# DDR_HDMI.net
KiCad netlist of a schematic drawn in Altium Designer
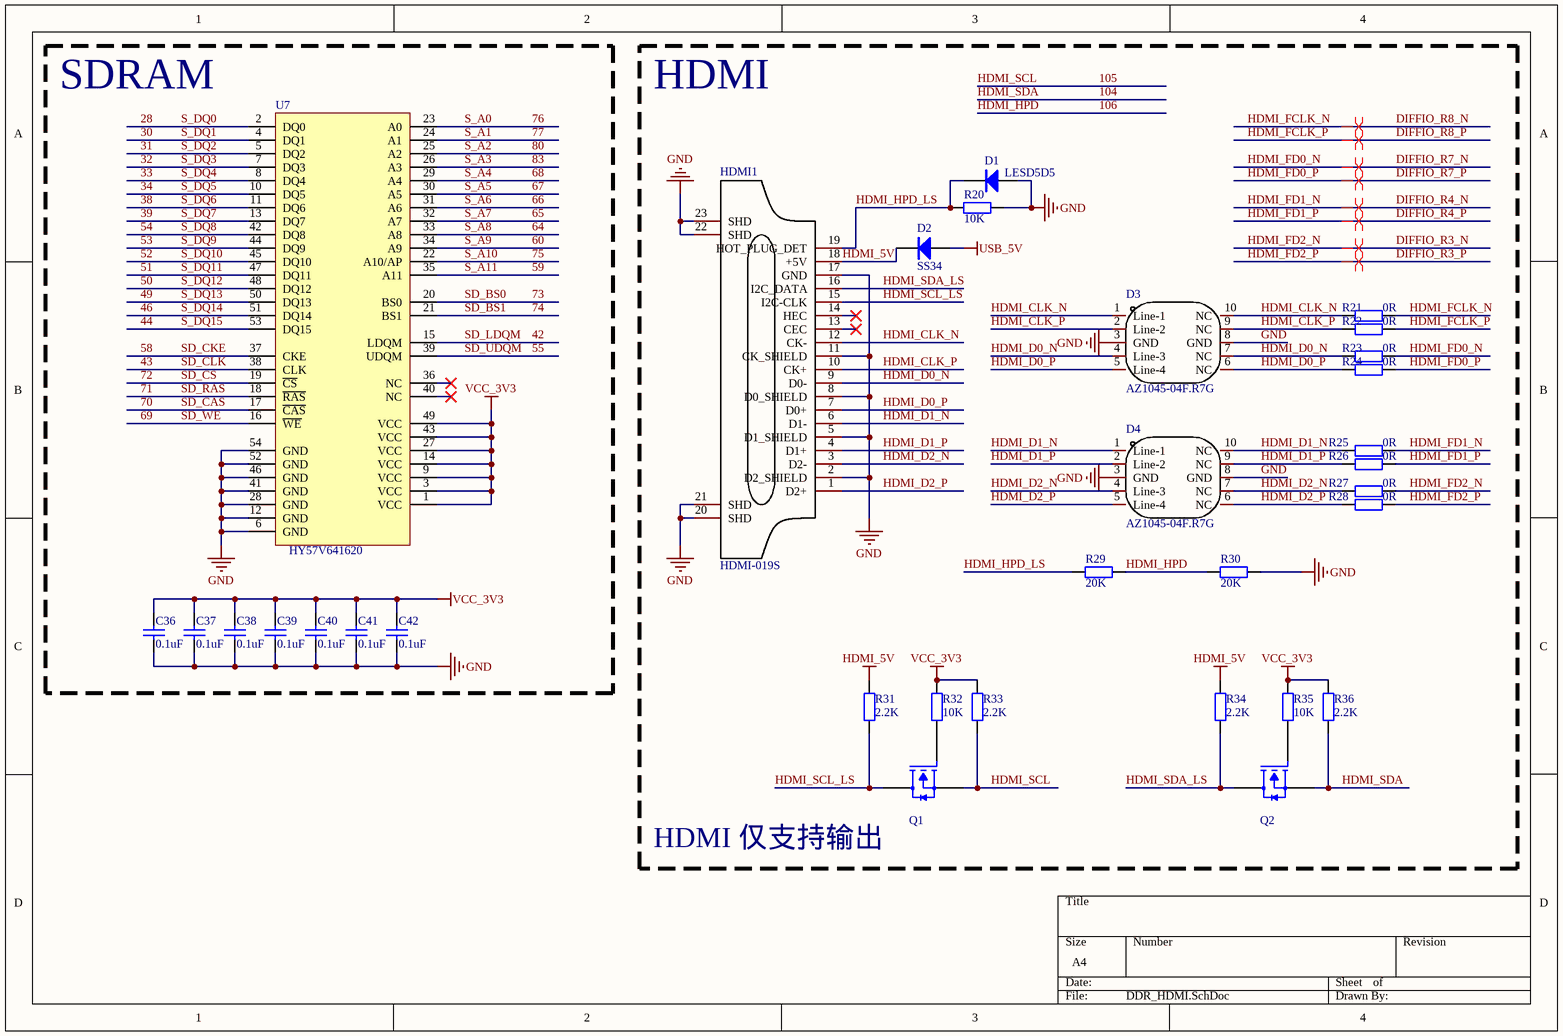
[diagram p0: DDR_HDMI.SchDoc]

(export (version "E")
  (design (tool "Eeschema 10.0.6"))
  (components
    (comp (ref "C36")
      (value "0.1uF")
      (footprint "0402_C")
      (description "贴片电容")
      (libsource (lib "My_Devices") (part "0402_C"))
    )
    (comp (ref "C37")
      (value "0.1uF")
      (footprint "0402_C")
      (description "贴片电容")
      (libsource (lib "My_Devices") (part "0402_C"))
    )
    (comp (ref "C38")
      (value "0.1uF")
      (footprint "0402_C")
      (description "贴片电容")
      (libsource (lib "My_Devices") (part "0402_C"))
    )
    (comp (ref "C39")
      (value "0.1uF")
      (footprint "0402_C")
      (description "贴片电容")
      (libsource (lib "My_Devices") (part "0402_C"))
    )
    (comp (ref "C40")
      (value "0.1uF")
      (footprint "0402_C")
      (description "贴片电容")
      (libsource (lib "My_Devices") (part "0402_C"))
    )
    (comp (ref "C41")
      (value "0.1uF")
      (footprint "0402_C")
      (description "贴片电容")
      (libsource (lib "My_Devices") (part "0402_C"))
    )
    (comp (ref "C42")
      (value "0.1uF")
      (footprint "0402_C")
      (description "贴片电容")
      (libsource (lib "My_Devices") (part "0402_C"))
    )
    (comp (ref "D1")
      (value "LESD5D5")
      (footprint "SOD-523_L1.2-W0.8-LS1.6-RD")
      (description "肖特基二极管")
      (fields (field (name "版权归属") "源创客"))
      (libsource (lib "My_Devices") (part "1N5819"))
    )
    (comp (ref "D2")
      (value "SS34")
      (footprint "SMC")
      (description "肖特基二极管")
      (fields (field (name "版权归属") "源创客"))
      (libsource (lib "My_Devices") (part "SS34"))
    )
    (comp (ref "D3")
      (value "AZ1045-04F.R7G")
      (footprint "DFN2510-10_L2.5-W1.0-P0.50-BL")
      (description "反向截止电压(Vrwm):5V;击穿电压:6V;最大钳位电压:12V;")
      (fields (field (name "MANUFACTURER") "AMAZING(晶焱)") (field (name "NAME") "AZ1045-04F.R7G"))
      (libsource (lib "Schlib1") (part "AZ1045-04F.R7G"))
    )
    (comp (ref "D4")
      (value "AZ1045-04F.R7G")
      (footprint "DFN2510-10_L2.5-W1.0-P0.50-BL")
      (description "反向截止电压(Vrwm):5V;击穿电压:6V;最大钳位电压:12V;")
      (fields (field (name "MANUFACTURER") "AMAZING(晶焱)") (field (name "NAME") "AZ1045-04F.R7G"))
      (libsource (lib "Schlib1") (part "AZ1045-04F.R7G"))
    )
    (comp (ref "HDMI1")
      (value "HDMI-019S")
      (footprint "HDMI-SMD_HDMI-019S")
      (description "连接器类型:HDMI;公母:母;总PIN位数:19;排数:-;安装方式:卧贴;额定电流:500mA;工作温度范围:-25℃~+75℃;")
      (fields (field (name "MANUFACTURER") "SOFNG(硕方)") (field (name "NAME") "HDMI-019S"))
      (libsource (lib "Schlib1") (part "HDMI-019S"))
    )
    (comp (ref "Q1")
      (value "AO3400A")
      (footprint "SOT23-3")
      (description "N-MOS")
      (libsource (lib "Schlib1") (part "AO3400A"))
    )
    (comp (ref "Q2")
      (value "AO3400A")
      (footprint "SOT23-3")
      (description "N-MOS")
      (libsource (lib "Schlib1") (part "AO3400A"))
    )
    (comp (ref "R20")
      (value "10K")
      (footprint "0402_R")
      (description "贴片电阻")
      (libsource (lib "") (part "0402_R_1"))
    )
    (comp (ref "R21")
      (value "0R")
      (footprint "0402_R")
      (description "贴片电阻")
      (libsource (lib "") (part "0402_R_1"))
    )
    (comp (ref "R22")
      (value "0R")
      (footprint "0402_R")
      (description "贴片电阻")
      (libsource (lib "") (part "0402_R_1"))
    )
    (comp (ref "R23")
      (value "0R")
      (footprint "0402_R")
      (description "贴片电阻")
      (libsource (lib "") (part "0402_R_1"))
    )
    (comp (ref "R24")
      (value "0R")
      (footprint "0402_R")
      (description "贴片电阻")
      (libsource (lib "") (part "0402_R_1"))
    )
    (comp (ref "R25")
      (value "0R")
      (footprint "0402_R")
      (description "贴片电阻")
      (libsource (lib "") (part "0402_R_1"))
    )
    (comp (ref "R26")
      (value "0R")
      (footprint "0402_R")
      (description "贴片电阻")
      (libsource (lib "") (part "0402_R_1"))
    )
    (comp (ref "R27")
      (value "0R")
      (footprint "0402_R")
      (description "贴片电阻")
      (libsource (lib "") (part "0402_R_1"))
    )
    (comp (ref "R28")
      (value "0R")
      (footprint "0402_R")
      (description "贴片电阻")
      (libsource (lib "") (part "0402_R_1"))
    )
    (comp (ref "R29")
      (value "20K")
      (footprint "0402_R")
      (description "贴片电阻")
      (libsource (lib "") (part "0402_R_1"))
    )
    (comp (ref "R30")
      (value "20K")
      (footprint "0402_R")
      (description "贴片电阻")
      (libsource (lib "") (part "0402_R_1"))
    )
    (comp (ref "R31")
      (value "2.2K")
      (footprint "0402_R")
      (description "贴片电阻")
      (libsource (lib "My_Devices") (part "0402_R"))
    )
    (comp (ref "R32")
      (value "10K")
      (footprint "0402_R")
      (description "贴片电阻")
      (libsource (lib "My_Devices") (part "0402_R"))
    )
    (comp (ref "R33")
      (value "2.2K")
      (footprint "0402_R")
      (description "贴片电阻")
      (libsource (lib "My_Devices") (part "0402_R"))
    )
    (comp (ref "R34")
      (value "2.2K")
      (footprint "0402_R")
      (description "贴片电阻")
      (libsource (lib "My_Devices") (part "0402_R"))
    )
    (comp (ref "R35")
      (value "10K")
      (footprint "0402_R")
      (description "贴片电阻")
      (libsource (lib "My_Devices") (part "0402_R"))
    )
    (comp (ref "R36")
      (value "2.2K")
      (footprint "0402_R")
      (description "贴片电阻")
      (libsource (lib "My_Devices") (part "0402_R"))
    )
    (comp (ref "U7")
      (value "HY57V641620")
      (footprint "TSOP-54_L22.2-W10.2-P0.80-LS11.8-BL")
      (libsource (lib "Schlib1") (part "HY57V641620"))
    )
  )
  (nets
    (net (code "1") (name "/28") (class "Default")
      (node (ref "U7") (pin "2") (pinfunction "DQ0_2") (pintype "passive"))
    )
    (net (code "2") (name "/30") (class "Default")
      (node (ref "U7") (pin "4") (pinfunction "DQ1_4") (pintype "passive"))
    )
    (net (code "3") (name "/31") (class "Default")
      (node (ref "U7") (pin "5") (pinfunction "DQ2_5") (pintype "passive"))
    )
    (net (code "4") (name "/32") (class "Default")
      (node (ref "U7") (pin "7") (pinfunction "DQ3_7") (pintype "passive"))
    )
    (net (code "5") (name "/33") (class "Default")
      (node (ref "U7") (pin "8") (pinfunction "DQ4_8") (pintype "passive"))
    )
    (net (code "6") (name "/34") (class "Default")
      (node (ref "U7") (pin "10") (pinfunction "DQ5_10") (pintype "passive"))
    )
    (net (code "7") (name "/38") (class "Default")
      (node (ref "U7") (pin "11") (pinfunction "DQ6_11") (pintype "passive"))
    )
    (net (code "8") (name "/39") (class "Default")
      (node (ref "U7") (pin "13") (pinfunction "DQ7_13") (pintype "passive"))
    )
    (net (code "9") (name "/42") (class "Default")
      (node (ref "U7") (pin "15") (pinfunction "LDQM_15") (pintype "power_in"))
    )
    (net (code "10") (name "/43") (class "Default")
      (node (ref "U7") (pin "38") (pinfunction "CLK_38") (pintype "passive"))
    )
    (net (code "11") (name "/44") (class "Default")
      (node (ref "U7") (pin "53") (pinfunction "DQ15_53") (pintype "passive"))
    )
    (net (code "12") (name "/46") (class "Default")
      (node (ref "U7") (pin "51") (pinfunction "DQ14_51") (pintype "passive"))
    )
    (net (code "13") (name "/49") (class "Default")
      (node (ref "U7") (pin "50") (pinfunction "DQ13_50") (pintype "passive"))
    )
    (net (code "14") (name "/50") (class "Default")
      (node (ref "U7") (pin "48") (pinfunction "DQ12_48") (pintype "passive"))
    )
    (net (code "15") (name "/51") (class "Default")
      (node (ref "U7") (pin "47") (pinfunction "DQ11_47") (pintype "passive"))
    )
    (net (code "16") (name "/52") (class "Default")
      (node (ref "U7") (pin "45") (pinfunction "DQ10_45") (pintype "passive"))
    )
    (net (code "17") (name "/53") (class "Default")
      (node (ref "U7") (pin "44") (pinfunction "DQ9_44") (pintype "passive"))
    )
    (net (code "18") (name "/54") (class "Default")
      (node (ref "U7") (pin "42") (pinfunction "DQ8_42") (pintype "passive"))
    )
    (net (code "19") (name "/55") (class "Default")
      (node (ref "U7") (pin "39") (pinfunction "UDQM_39") (pintype "power_in"))
    )
    (net (code "20") (name "/58") (class "Default")
      (node (ref "U7") (pin "37") (pinfunction "CKE_37") (pintype "passive"))
    )
    (net (code "21") (name "/59") (class "Default")
      (node (ref "U7") (pin "35") (pinfunction "A11_35") (pintype "power_in"))
    )
    (net (code "22") (name "/60") (class "Default")
      (node (ref "U7") (pin "34") (pinfunction "A9_34") (pintype "power_in"))
    )
    (net (code "23") (name "/64") (class "Default")
      (node (ref "U7") (pin "33") (pinfunction "A8_33") (pintype "power_in"))
    )
    (net (code "24") (name "/65") (class "Default")
      (node (ref "U7") (pin "32") (pinfunction "A7_32") (pintype "power_in"))
    )
    (net (code "25") (name "/66") (class "Default")
      (node (ref "U7") (pin "31") (pinfunction "A6_31") (pintype "power_in"))
    )
    (net (code "26") (name "/67") (class "Default")
      (node (ref "U7") (pin "30") (pinfunction "A5_30") (pintype "power_in"))
    )
    (net (code "27") (name "/68") (class "Default")
      (node (ref "U7") (pin "29") (pinfunction "A4_29") (pintype "power_in"))
    )
    (net (code "28") (name "/69") (class "Default")
      (node (ref "U7") (pin "16") (pinfunction "~{WE}_16") (pintype "power_in"))
    )
    (net (code "29") (name "/70") (class "Default")
      (node (ref "U7") (pin "17") (pinfunction "~{CAS}_17") (pintype "power_in"))
    )
    (net (code "30") (name "/71") (class "Default")
      (node (ref "U7") (pin "18") (pinfunction "~{RAS}_18") (pintype "power_in"))
    )
    (net (code "31") (name "/72") (class "Default")
      (node (ref "U7") (pin "19") (pinfunction "~{CS}_19") (pintype "passive"))
    )
    (net (code "32") (name "/73") (class "Default")
      (node (ref "U7") (pin "20") (pinfunction "BS0_20") (pintype "power_in"))
    )
    (net (code "33") (name "/74") (class "Default")
      (node (ref "U7") (pin "21") (pinfunction "BS1_21") (pintype "power_in"))
    )
    (net (code "34") (name "/75") (class "Default")
      (node (ref "U7") (pin "22") (pinfunction "A10/AP_22") (pintype "power_in"))
    )
    (net (code "35") (name "/76") (class "Default")
      (node (ref "U7") (pin "23") (pinfunction "A0_23") (pintype "power_in"))
    )
    (net (code "36") (name "/77") (class "Default")
      (node (ref "U7") (pin "24") (pinfunction "A1_24") (pintype "power_in"))
    )
    (net (code "37") (name "/80") (class "Default")
      (node (ref "U7") (pin "25") (pinfunction "A2_25") (pintype "power_in"))
    )
    (net (code "38") (name "/83") (class "Default")
      (node (ref "U7") (pin "26") (pinfunction "A3_26") (pintype "power_in"))
    )
    (net (code "39") (name "/104") (class "Default")
      (node (ref "Q2") (pin "2") (pinfunction "S_2") (pintype "passive"))
      (node (ref "R36") (pin "1") (pinfunction "1_1") (pintype "passive"))
    )
    (net (code "40") (name "/105") (class "Default")
      (node (ref "Q1") (pin "2") (pinfunction "S_2") (pintype "passive"))
      (node (ref "R33") (pin "1") (pinfunction "1_1") (pintype "passive"))
    )
    (net (code "41") (name "/106") (class "Default")
      (node (ref "R29") (pin "2") (pinfunction "2_2") (pintype "passive"))
      (node (ref "R30") (pin "1") (pinfunction "1_1") (pintype "passive"))
    )
    (net (code "42") (name "/DIFFIO_R3_N") (class "Default")
      (node (ref "R27") (pin "2") (pinfunction "2_2") (pintype "passive"))
    )
    (net (code "43") (name "/DIFFIO_R3_P") (class "Default")
      (node (ref "R28") (pin "2") (pinfunction "2_2") (pintype "passive"))
    )
    (net (code "44") (name "/DIFFIO_R4_N") (class "Default")
      (node (ref "R25") (pin "2") (pinfunction "2_2") (pintype "passive"))
    )
    (net (code "45") (name "/DIFFIO_R4_P") (class "Default")
      (node (ref "R26") (pin "2") (pinfunction "2_2") (pintype "passive"))
    )
    (net (code "46") (name "/DIFFIO_R7_N") (class "Default")
      (node (ref "R23") (pin "2") (pinfunction "2_2") (pintype "passive"))
    )
    (net (code "47") (name "/DIFFIO_R7_P") (class "Default")
      (node (ref "R24") (pin "2") (pinfunction "2_2") (pintype "passive"))
    )
    (net (code "48") (name "/DIFFIO_R8_N") (class "Default")
      (node (ref "R21") (pin "2") (pinfunction "2_2") (pintype "passive"))
    )
    (net (code "49") (name "/DIFFIO_R8_P") (class "Default")
      (node (ref "R22") (pin "2") (pinfunction "2_2") (pintype "passive"))
    )
    (net (code "50") (name "/HDMI_CLK_N") (class "Default")
      (node (ref "D3") (pin "1") (pinfunction "Line-1_1") (pintype "passive"))
      (node (ref "D3") (pin "10") (pinfunction "NC_10") (pintype "passive"))
      (node (ref "HDMI1") (pin "12") (pinfunction "CK-_12") (pintype "passive"))
      (node (ref "R21") (pin "1") (pinfunction "1_1") (pintype "passive"))
    )
    (net (code "51") (name "/HDMI_CLK_P") (class "Default")
      (node (ref "D3") (pin "2") (pinfunction "Line-2_2") (pintype "passive"))
      (node (ref "D3") (pin "9") (pinfunction "NC_9") (pintype "passive"))
      (node (ref "HDMI1") (pin "10") (pinfunction "CK+_10") (pintype "passive"))
      (node (ref "R22") (pin "1") (pinfunction "1_1") (pintype "passive"))
    )
    (net (code "52") (name "/HDMI_D0_N") (class "Default")
      (node (ref "D3") (pin "4") (pinfunction "Line-3_4") (pintype "passive"))
      (node (ref "D3") (pin "7") (pinfunction "NC_7") (pintype "passive"))
      (node (ref "HDMI1") (pin "9") (pinfunction "D0-_9") (pintype "passive"))
      (node (ref "R23") (pin "1") (pinfunction "1_1") (pintype "passive"))
    )
    (net (code "53") (name "/HDMI_D0_P") (class "Default")
      (node (ref "D3") (pin "5") (pinfunction "Line-4_5") (pintype "passive"))
      (node (ref "D3") (pin "6") (pinfunction "NC_6") (pintype "passive"))
      (node (ref "HDMI1") (pin "7") (pinfunction "D0+_7") (pintype "passive"))
      (node (ref "R24") (pin "1") (pinfunction "1_1") (pintype "passive"))
    )
    (net (code "54") (name "/HDMI_D1_N") (class "Default")
      (node (ref "D4") (pin "1") (pinfunction "Line-1_1") (pintype "passive"))
      (node (ref "D4") (pin "10") (pinfunction "NC_10") (pintype "passive"))
      (node (ref "HDMI1") (pin "6") (pinfunction "D1-_6") (pintype "passive"))
      (node (ref "R25") (pin "1") (pinfunction "1_1") (pintype "passive"))
    )
    (net (code "55") (name "/HDMI_D1_P") (class "Default")
      (node (ref "D4") (pin "2") (pinfunction "Line-2_2") (pintype "passive"))
      (node (ref "D4") (pin "9") (pinfunction "NC_9") (pintype "passive"))
      (node (ref "HDMI1") (pin "4") (pinfunction "D1+_4") (pintype "passive"))
      (node (ref "R26") (pin "1") (pinfunction "1_1") (pintype "passive"))
    )
    (net (code "56") (name "/HDMI_D2_N") (class "Default")
      (node (ref "D4") (pin "4") (pinfunction "Line-3_4") (pintype "passive"))
      (node (ref "D4") (pin "7") (pinfunction "NC_7") (pintype "passive"))
      (node (ref "HDMI1") (pin "3") (pinfunction "D2-_3") (pintype "passive"))
      (node (ref "R27") (pin "1") (pinfunction "1_1") (pintype "passive"))
    )
    (net (code "57") (name "/HDMI_D2_P") (class "Default")
      (node (ref "D4") (pin "5") (pinfunction "Line-4_5") (pintype "passive"))
      (node (ref "D4") (pin "6") (pinfunction "NC_6") (pintype "passive"))
      (node (ref "HDMI1") (pin "1") (pinfunction "D2+_1") (pintype "passive"))
      (node (ref "R28") (pin "1") (pinfunction "1_1") (pintype "passive"))
    )
    (net (code "58") (name "/HDMI_HPD_LS") (class "Default")
      (node (ref "D1") (pin "2") (pinfunction "K_2") (pintype "passive"))
      (node (ref "HDMI1") (pin "19") (pinfunction "HOT_PLUG_DET_19") (pintype "passive"))
      (node (ref "R20") (pin "1") (pinfunction "1_1") (pintype "passive"))
      (node (ref "R29") (pin "1") (pinfunction "1_1") (pintype "passive"))
    )
    (net (code "59") (name "/HDMI_SCL_LS") (class "Default")
      (node (ref "HDMI1") (pin "15") (pinfunction "I2C-CLK_15") (pintype "passive"))
      (node (ref "Q1") (pin "3") (pinfunction "D_3") (pintype "passive"))
      (node (ref "R31") (pin "1") (pinfunction "1_1") (pintype "passive"))
    )
    (net (code "60") (name "/HDMI_SDA_LS") (class "Default")
      (node (ref "HDMI1") (pin "16") (pinfunction "I2C_DATA_16") (pintype "passive"))
      (node (ref "Q2") (pin "3") (pinfunction "D_3") (pintype "passive"))
      (node (ref "R34") (pin "1") (pinfunction "1_1") (pintype "passive"))
    )
    (net (code "61") (name "GND") (class "Default")
      (node (ref "C36") (pin "1") (pinfunction "1_1") (pintype "passive"))
      (node (ref "C37") (pin "1") (pinfunction "1_1") (pintype "passive"))
      (node (ref "C38") (pin "1") (pinfunction "1_1") (pintype "passive"))
      (node (ref "C39") (pin "1") (pinfunction "1_1") (pintype "passive"))
      (node (ref "C40") (pin "1") (pinfunction "1_1") (pintype "passive"))
      (node (ref "C41") (pin "1") (pinfunction "1_1") (pintype "passive"))
      (node (ref "C42") (pin "1") (pinfunction "1_1") (pintype "passive"))
      (node (ref "D1") (pin "1") (pinfunction "A_1") (pintype "passive"))
      (node (ref "D3") (pin "3") (pinfunction "GND_3") (pintype "passive"))
      (node (ref "D3") (pin "8") (pinfunction "GND_8") (pintype "passive"))
      (node (ref "D4") (pin "3") (pinfunction "GND_3") (pintype "passive"))
      (node (ref "D4") (pin "8") (pinfunction "GND_8") (pintype "passive"))
      (node (ref "HDMI1") (pin "11") (pinfunction "CK_SHIELD_11") (pintype "passive"))
      (node (ref "HDMI1") (pin "17") (pinfunction "GND_17") (pintype "passive"))
      (node (ref "HDMI1") (pin "2") (pinfunction "D2_SHIELD_2") (pintype "passive"))
      (node (ref "HDMI1") (pin "20") (pinfunction "SHD_20") (pintype "passive"))
      (node (ref "HDMI1") (pin "21") (pinfunction "SHD_21") (pintype "passive"))
      (node (ref "HDMI1") (pin "22") (pinfunction "SHD_22") (pintype "passive"))
      (node (ref "HDMI1") (pin "23") (pinfunction "SHD_23") (pintype "passive"))
      (node (ref "HDMI1") (pin "5") (pinfunction "D1_SHIELD_5") (pintype "passive"))
      (node (ref "HDMI1") (pin "8") (pinfunction "D0_SHIELD_8") (pintype "passive"))
      (node (ref "R20") (pin "2") (pinfunction "2_2") (pintype "passive"))
      (node (ref "R30") (pin "2") (pinfunction "2_2") (pintype "passive"))
      (node (ref "U7") (pin "12") (pinfunction "GND_12") (pintype "power_in"))
      (node (ref "U7") (pin "28") (pinfunction "GND_28") (pintype "power_in"))
      (node (ref "U7") (pin "41") (pinfunction "GND_41") (pintype "power_in"))
      (node (ref "U7") (pin "46") (pinfunction "GND_46") (pintype "power_in"))
      (node (ref "U7") (pin "52") (pinfunction "GND_52") (pintype "power_in"))
      (node (ref "U7") (pin "54") (pinfunction "GND_54") (pintype "power_in"))
      (node (ref "U7") (pin "6") (pinfunction "GND_6") (pintype "power_in"))
    )
    (net (code "62") (name "HDMI_5V") (class "Default")
      (node (ref "D2") (pin "2") (pinfunction "K_2") (pintype "passive"))
      (node (ref "HDMI1") (pin "18") (pinfunction "+5V_18") (pintype "passive"))
      (node (ref "R31") (pin "2") (pinfunction "2_2") (pintype "passive"))
      (node (ref "R34") (pin "2") (pinfunction "2_2") (pintype "passive"))
    )
    (net (code "63") (name "Net-(Q1-G)") (class "Default")
      (node (ref "Q1") (pin "1") (pinfunction "G_1") (pintype "passive"))
      (node (ref "R32") (pin "1") (pinfunction "1_1") (pintype "passive"))
    )
    (net (code "64") (name "Net-(Q2-G)") (class "Default")
      (node (ref "Q2") (pin "1") (pinfunction "G_1") (pintype "passive"))
      (node (ref "R35") (pin "1") (pinfunction "1_1") (pintype "passive"))
    )
    (net (code "65") (name "USB_5V") (class "Default")
      (node (ref "D2") (pin "1") (pinfunction "A_1") (pintype "passive"))
    )
    (net (code "66") (name "VCC_3V3") (class "Default")
      (node (ref "C36") (pin "2") (pinfunction "2_2") (pintype "passive"))
      (node (ref "C37") (pin "2") (pinfunction "2_2") (pintype "passive"))
      (node (ref "C38") (pin "2") (pinfunction "2_2") (pintype "passive"))
      (node (ref "C39") (pin "2") (pinfunction "2_2") (pintype "passive"))
      (node (ref "C40") (pin "2") (pinfunction "2_2") (pintype "passive"))
      (node (ref "C41") (pin "2") (pinfunction "2_2") (pintype "passive"))
      (node (ref "C42") (pin "2") (pinfunction "2_2") (pintype "passive"))
      (node (ref "R32") (pin "2") (pinfunction "2_2") (pintype "passive"))
      (node (ref "R33") (pin "2") (pinfunction "2_2") (pintype "passive"))
      (node (ref "R35") (pin "2") (pinfunction "2_2") (pintype "passive"))
      (node (ref "R36") (pin "2") (pinfunction "2_2") (pintype "passive"))
      (node (ref "U7") (pin "1") (pinfunction "VCC_1") (pintype "power_in"))
      (node (ref "U7") (pin "14") (pinfunction "VCC_14") (pintype "power_in"))
      (node (ref "U7") (pin "27") (pinfunction "VCC_27") (pintype "power_in"))
      (node (ref "U7") (pin "3") (pinfunction "VCC_3") (pintype "power_in"))
      (node (ref "U7") (pin "43") (pinfunction "VCC_43") (pintype "power_in"))
      (node (ref "U7") (pin "49") (pinfunction "VCC_49") (pintype "power_in"))
      (node (ref "U7") (pin "9") (pinfunction "VCC_9") (pintype "power_in"))
    )
    (net (code "67") (name "unconnected-(HDMI1-CEC-Pad13)") (class "Default")
      (node (ref "HDMI1") (pin "13") (pinfunction "CEC_13") (pintype "passive+no_connect"))
    )
    (net (code "68") (name "unconnected-(HDMI1-HEC-Pad14)") (class "Default")
      (node (ref "HDMI1") (pin "14") (pinfunction "HEC_14") (pintype "passive+no_connect"))
    )
    (net (code "69") (name "unconnected-(U7-NC-Pad36)") (class "Default")
      (node (ref "U7") (pin "36") (pinfunction "NC_36") (pintype "power_in+no_connect"))
    )
    (net (code "70") (name "unconnected-(U7-NC-Pad40)") (class "Default")
      (node (ref "U7") (pin "40") (pinfunction "NC_40") (pintype "power_in+no_connect"))
    )
  )
)
